# cociclo_wemos_2016_final_2.net
KiCad netlist of a schematic drawn in EAGLE
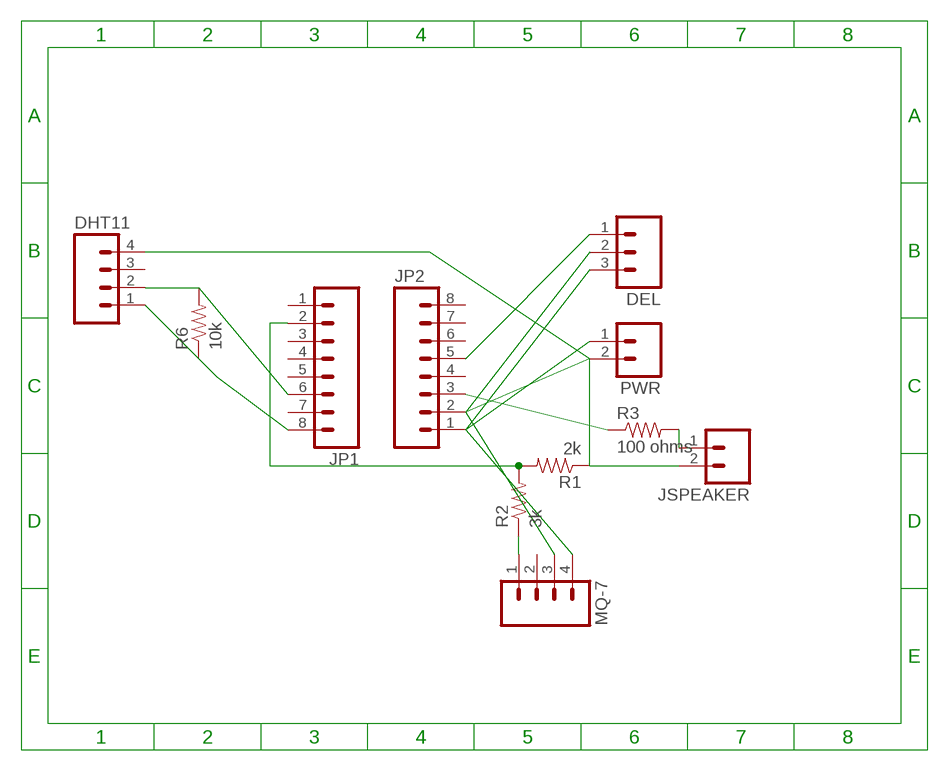
[diagram p0: schematic, sheet 1]

(export (version "E")
  (design (tool "Eeschema 10.0.6"))
  (components
    (comp (ref "DEL")
      (value "M03PTH")
      (footprint "eagle-import:1X03")
      (libsource (lib "eagle-import") (part "M03PTH"))
    )
    (comp (ref "DHT11")
      (value "M04PTH")
      (footprint "eagle-import:1X04")
      (libsource (lib "eagle-import") (part "M04PTH"))
    )
    (comp (ref "JP1")
      (value "M08")
      (footprint "eagle-import:1X08_ROUND")
      (libsource (lib "eagle-import") (part "M08"))
    )
    (comp (ref "JP2")
      (value "M08")
      (footprint "eagle-import:1X08_ROUND")
      (libsource (lib "eagle-import") (part "M08"))
    )
    (comp (ref "JSPEAKER")
      (value "M02PTH")
      (footprint "eagle-import:1X02")
      (libsource (lib "eagle-import") (part "M02PTH"))
    )
    (comp (ref "MQ-7")
      (value "M04PTH")
      (footprint "eagle-import:1X04")
      (libsource (lib "eagle-import") (part "M04PTH"))
    )
    (comp (ref "PWR")
      (value "M02LOCK_LONGPADS")
      (footprint "eagle-import:1X02_LOCK_LONGPADS")
      (libsource (lib "eagle-import") (part "M02LOCK_LONGPADS"))
    )
    (comp (ref "R1")
      (value "2k")
      (footprint "eagle-import:1206")
      (libsource (lib "eagle-import") (part "RESISTOR1206"))
    )
    (comp (ref "R2")
      (value "3k")
      (footprint "eagle-import:1206")
      (libsource (lib "eagle-import") (part "RESISTOR1206"))
    )
    (comp (ref "R3")
      (value "100 ohms")
      (footprint "eagle-import:1206")
      (libsource (lib "eagle-import") (part "RESISTOR1206"))
    )
    (comp (ref "R6")
      (value "10k")
      (footprint "eagle-import:1206")
      (libsource (lib "eagle-import") (part "RESISTOR1206"))
    )
  )
  (nets
    (net (code "1") (name "Net-(DEL-Pad1)") (class "Default")
      (node (ref "DEL") (pin "1") (pinfunction "1_1") (pintype "passive"))
      (node (ref "JP2") (pin "5") (pinfunction "5_5") (pintype "passive"))
    )
    (net (code "2") (name "Net-(DEL-Pad2)") (class "Default")
      (node (ref "DEL") (pin "2") (pinfunction "2_2") (pintype "passive"))
      (node (ref "DHT11") (pin "4") (pinfunction "4_4") (pintype "passive"))
      (node (ref "JP2") (pin "2") (pinfunction "2_2") (pintype "passive"))
      (node (ref "JSPEAKER") (pin "2") (pinfunction "2_2") (pintype "passive"))
      (node (ref "MQ-7") (pin "3") (pinfunction "3_3") (pintype "passive"))
      (node (ref "PWR") (pin "2") (pinfunction "2_2") (pintype "passive"))
      (node (ref "R1") (pin "1") (pinfunction "1_1") (pintype "passive"))
    )
    (net (code "3") (name "Net-(DEL-Pad3)") (class "Default")
      (node (ref "DEL") (pin "3") (pinfunction "3_3") (pintype "passive"))
      (node (ref "JP2") (pin "1") (pinfunction "1_1") (pintype "passive"))
      (node (ref "MQ-7") (pin "4") (pinfunction "4_4") (pintype "passive"))
      (node (ref "PWR") (pin "1") (pinfunction "1_1") (pintype "passive"))
    )
    (net (code "4") (name "Net-(DHT11-Pad1)") (class "Default")
      (node (ref "DHT11") (pin "1") (pinfunction "1_1") (pintype "passive"))
      (node (ref "JP1") (pin "8") (pinfunction "8_8") (pintype "passive"))
      (node (ref "R6") (pin "1") (pinfunction "1_1") (pintype "passive"))
    )
    (net (code "5") (name "Net-(DHT11-Pad2)") (class "Default")
      (node (ref "DHT11") (pin "2") (pinfunction "2_2") (pintype "passive"))
      (node (ref "JP1") (pin "6") (pinfunction "6_6") (pintype "passive"))
      (node (ref "R6") (pin "2") (pinfunction "2_2") (pintype "passive"))
    )
    (net (code "6") (name "Net-(JP1-Pad2)") (class "Default")
      (node (ref "JP1") (pin "2") (pinfunction "2_2") (pintype "passive"))
      (node (ref "R1") (pin "2") (pinfunction "2_2") (pintype "passive"))
      (node (ref "R2") (pin "2") (pinfunction "2_2") (pintype "passive"))
    )
    (net (code "7") (name "Net-(JP2-Pad3)") (class "Default")
      (node (ref "JP2") (pin "3") (pinfunction "3_3") (pintype "passive"))
      (node (ref "R3") (pin "1") (pinfunction "1_1") (pintype "passive"))
    )
    (net (code "8") (name "Net-(JSPEAKER-Pad1)") (class "Default")
      (node (ref "JSPEAKER") (pin "1") (pinfunction "1_1") (pintype "passive"))
      (node (ref "R3") (pin "2") (pinfunction "2_2") (pintype "passive"))
    )
    (net (code "9") (name "Net-(MQ-7-Pad1)") (class "Default")
      (node (ref "MQ-7") (pin "1") (pinfunction "1_1") (pintype "passive"))
      (node (ref "R2") (pin "1") (pinfunction "1_1") (pintype "passive"))
    )
    (net (code "10") (name "unconnected-(DHT11-Pad3)") (class "Default")
      (node (ref "DHT11") (pin "3") (pinfunction "3_3") (pintype "passive"))
    )
    (net (code "11") (name "unconnected-(JP1-Pad1)") (class "Default")
      (node (ref "JP1") (pin "1") (pinfunction "1_1") (pintype "passive"))
    )
    (net (code "12") (name "unconnected-(JP1-Pad3)") (class "Default")
      (node (ref "JP1") (pin "3") (pinfunction "3_3") (pintype "passive"))
    )
    (net (code "13") (name "unconnected-(JP1-Pad4)") (class "Default")
      (node (ref "JP1") (pin "4") (pinfunction "4_4") (pintype "passive"))
    )
    (net (code "14") (name "unconnected-(JP1-Pad5)") (class "Default")
      (node (ref "JP1") (pin "5") (pinfunction "5_5") (pintype "passive"))
    )
    (net (code "15") (name "unconnected-(JP1-Pad7)") (class "Default")
      (node (ref "JP1") (pin "7") (pinfunction "7_7") (pintype "passive"))
    )
    (net (code "16") (name "unconnected-(JP2-Pad4)") (class "Default")
      (node (ref "JP2") (pin "4") (pinfunction "4_4") (pintype "passive"))
    )
    (net (code "17") (name "unconnected-(JP2-Pad6)") (class "Default")
      (node (ref "JP2") (pin "6") (pinfunction "6_6") (pintype "passive"))
    )
    (net (code "18") (name "unconnected-(JP2-Pad7)") (class "Default")
      (node (ref "JP2") (pin "7") (pinfunction "7_7") (pintype "passive"))
    )
    (net (code "19") (name "unconnected-(JP2-Pad8)") (class "Default")
      (node (ref "JP2") (pin "8") (pinfunction "8_8") (pintype "passive"))
    )
    (net (code "20") (name "unconnected-(MQ-7-Pad2)") (class "Default")
      (node (ref "MQ-7") (pin "2") (pinfunction "2_2") (pintype "passive"))
    )
  )
)
